# USB.net
KiCad netlist of a schematic drawn in Altium Designer
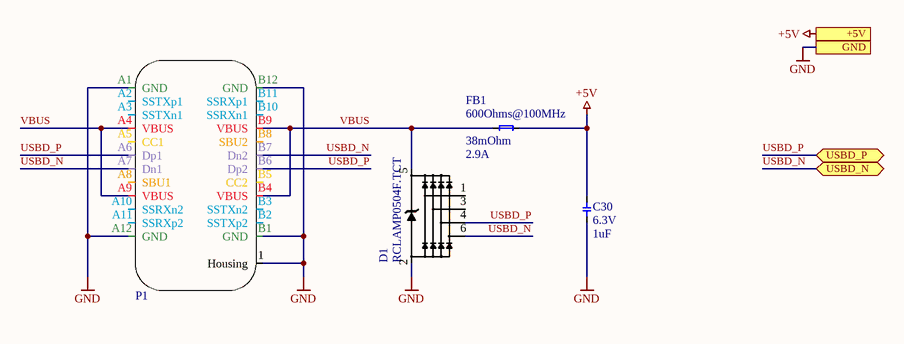
[diagram p0: USB.SchDoc]

(export (version "E")
  (design (tool "Eeschema 10.0.6"))
  (components
    (comp (ref "C30")
      (value "1uF")
      (footprint "CX7R0603K")
      (description "SMD Capacitor")
      (fields (field (name "VALUE2") "6.3V") (field (name "Comment") "06036C105JAT2A"))
      (libsource (lib "ChaoticCircuits") (part "kyocera-C-X7R-0603"))
    )
    (comp (ref "D1")
      (value "RCLAMP0504F.TCT")
      (footprint "SOT23-6L_0.65_C")
      (description "23V Clamp 6A (8/20µs) Ipp Tvs Diode Surface Mount SC-70-6")
      (libsource (lib "ChaoticCircuits") (part "RCLAMP0504F.TCT"))
    )
    (comp (ref "FB1")
      (value "BLM31KN601SN1L")
      (footprint "BLM31KN_SN_1206_C")
      (description "600 Ohms @ 100 MHz 1 Power Line Ferrite Bead 1206 (3216 Metric) 2.9A 38mOhm")
      (fields
        (field (name "DCR") "38mOhm")
        (field (name "CURRENT") "2.9A")
        (field (name "IMPEDANCE") "600Ohms@100MHz")
      )
      (libsource (lib "ChaoticCircuits") (part "BLM31KN601SN1L"))
    )
    (comp (ref "P1")
      (value "10132328-10011LF")
      (footprint "USB_TYPEC_VERTICAL_10132328-10011LF")
      (libsource (lib "ChaoticCircuits") (part "10132328-10011LF"))
    )
  )
  (nets
    (net (code "1") (name "+5V") (class "Default")
      (node (ref "C30") (pin "2") (pinfunction "2_2") (pintype "passive"))
      (node (ref "FB1") (pin "2") (pinfunction "2_2") (pintype "passive"))
    )
    (net (code "2") (name "/USBD_N") (class "Default")
      (node (ref "D1") (pin "6") (pinfunction "6_6") (pintype "passive"))
      (node (ref "P1") (pin "A7") (pinfunction "Dn1_A7") (pintype "passive"))
      (node (ref "P1") (pin "B7") (pinfunction "Dn2_B7") (pintype "passive"))
    )
    (net (code "3") (name "/USBD_P") (class "Default")
      (node (ref "D1") (pin "4") (pinfunction "4_4") (pintype "passive"))
      (node (ref "P1") (pin "A6") (pinfunction "Dp1_A6") (pintype "passive"))
      (node (ref "P1") (pin "B6") (pinfunction "Dp2_B6") (pintype "passive"))
    )
    (net (code "4") (name "/VBUS") (class "Default")
      (node (ref "D1") (pin "5") (pinfunction "5_5") (pintype "passive"))
      (node (ref "FB1") (pin "1") (pinfunction "1_1") (pintype "passive"))
      (node (ref "P1") (pin "A4") (pinfunction "VBUS_A4") (pintype "passive"))
      (node (ref "P1") (pin "A9") (pinfunction "VBUS_A9") (pintype "passive"))
      (node (ref "P1") (pin "B4") (pinfunction "VBUS_B4") (pintype "passive"))
      (node (ref "P1") (pin "B9") (pinfunction "VBUS_B9") (pintype "passive"))
    )
    (net (code "5") (name "GND") (class "Default")
      (node (ref "C30") (pin "1") (pinfunction "1_1") (pintype "passive"))
      (node (ref "D1") (pin "2") (pinfunction "2_2") (pintype "passive"))
      (node (ref "P1") (pin "1") (pinfunction "Housing_1") (pintype "passive"))
      (node (ref "P1") (pin "A1") (pinfunction "GND_A1") (pintype "passive"))
      (node (ref "P1") (pin "A12") (pinfunction "GND_A12") (pintype "passive"))
      (node (ref "P1") (pin "B1") (pinfunction "GND_B1") (pintype "passive"))
      (node (ref "P1") (pin "B12") (pinfunction "GND_B12") (pintype "passive"))
    )
    (net (code "6") (name "unconnected-(D1-Pad1)") (class "Default")
      (node (ref "D1") (pin "1") (pinfunction "1_1") (pintype "passive"))
    )
    (net (code "7") (name "unconnected-(D1-Pad3)") (class "Default")
      (node (ref "D1") (pin "3") (pinfunction "3_3") (pintype "passive"))
    )
    (net (code "8") (name "unconnected-(P1-CC1-PadA5)") (class "Default")
      (node (ref "P1") (pin "A5") (pinfunction "CC1_A5") (pintype "passive"))
    )
    (net (code "9") (name "unconnected-(P1-CC2-PadB5)") (class "Default")
      (node (ref "P1") (pin "B5") (pinfunction "CC2_B5") (pintype "passive"))
    )
    (net (code "10") (name "unconnected-(P1-SBU1-PadA8)") (class "Default")
      (node (ref "P1") (pin "A8") (pinfunction "SBU1_A8") (pintype "passive"))
    )
    (net (code "11") (name "unconnected-(P1-SBU2-PadB8)") (class "Default")
      (node (ref "P1") (pin "B8") (pinfunction "SBU2_B8") (pintype "passive"))
    )
    (net (code "12") (name "unconnected-(P1-SSRXn1-PadB10)") (class "Default")
      (node (ref "P1") (pin "B10") (pinfunction "SSRXn1_B10") (pintype "passive"))
    )
    (net (code "13") (name "unconnected-(P1-SSRXn2-PadA10)") (class "Default")
      (node (ref "P1") (pin "A10") (pinfunction "SSRXn2_A10") (pintype "passive"))
    )
    (net (code "14") (name "unconnected-(P1-SSRXp1-PadB11)") (class "Default")
      (node (ref "P1") (pin "B11") (pinfunction "SSRXp1_B11") (pintype "passive"))
    )
    (net (code "15") (name "unconnected-(P1-SSRXp2-PadA11)") (class "Default")
      (node (ref "P1") (pin "A11") (pinfunction "SSRXp2_A11") (pintype "passive"))
    )
    (net (code "16") (name "unconnected-(P1-SSTXn1-PadA3)") (class "Default")
      (node (ref "P1") (pin "A3") (pinfunction "SSTXn1_A3") (pintype "passive"))
    )
    (net (code "17") (name "unconnected-(P1-SSTXn2-PadB3)") (class "Default")
      (node (ref "P1") (pin "B3") (pinfunction "SSTXn2_B3") (pintype "passive"))
    )
    (net (code "18") (name "unconnected-(P1-SSTXp1-PadA2)") (class "Default")
      (node (ref "P1") (pin "A2") (pinfunction "SSTXp1_A2") (pintype "passive"))
    )
    (net (code "19") (name "unconnected-(P1-SSTXp2-PadB2)") (class "Default")
      (node (ref "P1") (pin "B2") (pinfunction "SSTXp2_B2") (pintype "passive"))
    )
  )
)
